# motoko_ice_dragon_x_bldc.net
KiCad netlist of a schematic drawn in EAGLE
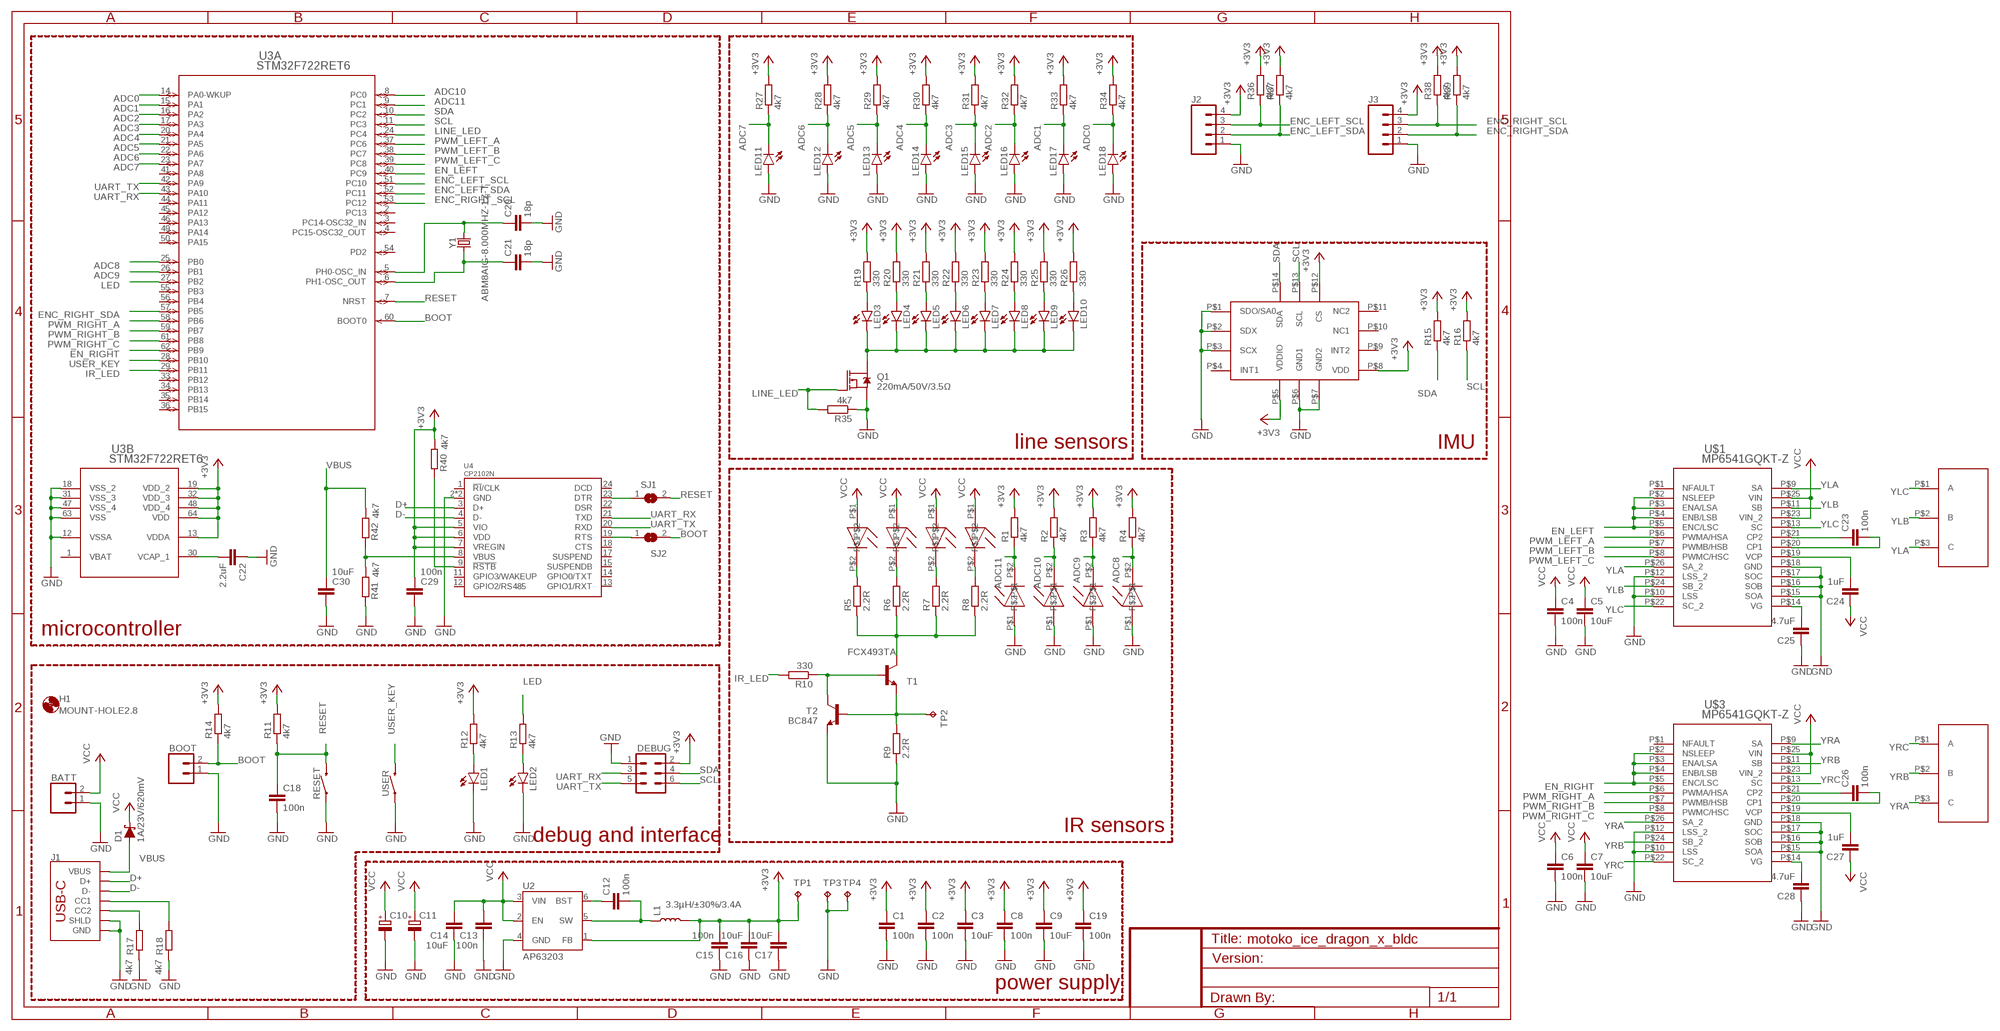
[diagram p0: schematic, sheet 1]

(export (version "E")
  (design (tool "Eeschema 10.0.6"))
  (components
    (comp (ref "BATT")
      (value "CONN_02LOCK_LONGPADS")
      (footprint "eagle-import:1X02_LOCK_LONGPADS")
      (libsource (lib "eagle-import") (part "CONN_02LOCK_LONGPADS"))
    )
    (comp (ref "BOOT")
      (value "CONN_02LOCK_LONGPADS")
      (footprint "eagle-import:1X02_LOCK_LONGPADS")
      (libsource (lib "eagle-import") (part "CONN_02LOCK_LONGPADS"))
    )
    (comp (ref "C1")
      (value "100n")
      (footprint "eagle-import:C0805")
      (libsource (lib "eagle-import") (part "C-EUC0805"))
    )
    (comp (ref "C2")
      (value "100n")
      (footprint "eagle-import:C0805")
      (libsource (lib "eagle-import") (part "C-EUC0805"))
    )
    (comp (ref "C3")
      (value "10uF")
      (footprint "eagle-import:C0805")
      (libsource (lib "eagle-import") (part "C-EUC0805"))
    )
    (comp (ref "C4")
      (value "100n")
      (footprint "eagle-import:C0805")
      (libsource (lib "eagle-import") (part "C-EUC0805"))
    )
    (comp (ref "C5")
      (value "10uF")
      (footprint "eagle-import:C0805")
      (libsource (lib "eagle-import") (part "C-EUC0805"))
    )
    (comp (ref "C6")
      (value "100n")
      (footprint "eagle-import:C0805")
      (libsource (lib "eagle-import") (part "C-EUC0805"))
    )
    (comp (ref "C7")
      (value "10uF")
      (footprint "eagle-import:C0805")
      (libsource (lib "eagle-import") (part "C-EUC0805"))
    )
    (comp (ref "C8")
      (value "100n")
      (footprint "eagle-import:C0805")
      (libsource (lib "eagle-import") (part "C-EUC0805"))
    )
    (comp (ref "C9")
      (value "10uF")
      (footprint "eagle-import:C0805")
      (libsource (lib "eagle-import") (part "C-EUC0805"))
    )
    (comp (ref "C10")
      (value "CPOL-EU140CLH-0810")
      (footprint "eagle-import:140CLH-0810")
      (libsource (lib "eagle-import") (part "CPOL-EU140CLH-0810"))
    )
    (comp (ref "C11")
      (value "CPOL-EU140CLH-0810")
      (footprint "eagle-import:140CLH-0810")
      (libsource (lib "eagle-import") (part "CPOL-EU140CLH-0810"))
    )
    (comp (ref "C12")
      (value "100n")
      (footprint "eagle-import:C0805")
      (libsource (lib "eagle-import") (part "C-EUC0805"))
    )
    (comp (ref "C13")
      (value "100n")
      (footprint "eagle-import:C0805")
      (libsource (lib "eagle-import") (part "C-EUC0805"))
    )
    (comp (ref "C14")
      (value "10uF")
      (footprint "eagle-import:C0805")
      (libsource (lib "eagle-import") (part "C-EUC0805"))
    )
    (comp (ref "C15")
      (value "100n")
      (footprint "eagle-import:C0805")
      (libsource (lib "eagle-import") (part "C-EUC0805"))
    )
    (comp (ref "C16")
      (value "10uF")
      (footprint "eagle-import:C0805")
      (libsource (lib "eagle-import") (part "C-EUC0805"))
    )
    (comp (ref "C17")
      (value "10uF")
      (footprint "eagle-import:C0805")
      (libsource (lib "eagle-import") (part "C-EUC0805"))
    )
    (comp (ref "C18")
      (value "100n")
      (footprint "eagle-import:C0805")
      (libsource (lib "eagle-import") (part "C-EUC0805"))
    )
    (comp (ref "C19")
      (value "100n")
      (footprint "eagle-import:C0805")
      (libsource (lib "eagle-import") (part "C-EUC0805"))
    )
    (comp (ref "C20")
      (value "18p")
      (footprint "eagle-import:C0805")
      (libsource (lib "eagle-import") (part "C-EUC0805"))
    )
    (comp (ref "C21")
      (value "18p")
      (footprint "eagle-import:C0805")
      (libsource (lib "eagle-import") (part "C-EUC0805"))
    )
    (comp (ref "C22")
      (value "2.2uF")
      (footprint "eagle-import:C0805")
      (libsource (lib "eagle-import") (part "C-EUC0805"))
    )
    (comp (ref "C23")
      (value "100n")
      (footprint "eagle-import:C0805")
      (libsource (lib "eagle-import") (part "C-EUC0805"))
    )
    (comp (ref "C24")
      (value "1uF")
      (footprint "eagle-import:C0805")
      (libsource (lib "eagle-import") (part "C-EUC0805"))
    )
    (comp (ref "C25")
      (value "4.7uF")
      (footprint "eagle-import:C0805")
      (libsource (lib "eagle-import") (part "C-EUC0805"))
    )
    (comp (ref "C26")
      (value "100n")
      (footprint "eagle-import:C0805")
      (libsource (lib "eagle-import") (part "C-EUC0805"))
    )
    (comp (ref "C27")
      (value "1uF")
      (footprint "eagle-import:C0805")
      (libsource (lib "eagle-import") (part "C-EUC0805"))
    )
    (comp (ref "C28")
      (value "4.7uF")
      (footprint "eagle-import:C0805")
      (libsource (lib "eagle-import") (part "C-EUC0805"))
    )
    (comp (ref "C29")
      (value "100n")
      (footprint "eagle-import:C0805")
      (libsource (lib "eagle-import") (part "C-EUC0805"))
    )
    (comp (ref "C30")
      (value "10uF")
      (footprint "eagle-import:C0805")
      (libsource (lib "eagle-import") (part "C-EUC0805"))
    )
    (comp (ref "D1")
      (value "1A/23V/620mV")
      (footprint "eagle-import:SOD-323")
      (libsource (lib "eagle-import") (part "DIODE-SCHOTTKY-BAT20J"))
    )
    (comp (ref "DEBUG")
      (value "FEMALE 2x3")
      (footprint "eagle-import:2X3")
      (libsource (lib "eagle-import") (part "CONN_03X2FEMALE"))
    )
    (comp (ref "H1")
      (value "MOUNT-HOLE2.8")
      (footprint "eagle-import:2,8")
      (libsource (lib "eagle-import") (part "MOUNT-HOLE2.8"))
    )
    (comp (ref "J1")
      (value "640-USB4105-GF-A-120, man. GCT")
      (footprint "eagle-import:USB-C-16P-2LAYER-PADS")
      (libsource (lib "eagle-import") (part "USB_C_2-LAYER_PADS"))
    )
    (comp (ref "J2")
      (value "CONN_04LONGPADS")
      (footprint "eagle-import:1X04_LONGPADS")
      (libsource (lib "eagle-import") (part "CONN_04LONGPADS"))
    )
    (comp (ref "J3")
      (value "CONN_04LONGPADS")
      (footprint "eagle-import:1X04_LONGPADS")
      (libsource (lib "eagle-import") (part "CONN_04LONGPADS"))
    )
    (comp (ref "L1")
      (value "3.3µH/±30%/3.4A")
      (footprint "eagle-import:CR54")
      (libsource (lib "eagle-import") (part "INDUCTOR-CR54-3.3UH"))
    )
    (comp (ref "LED1")
      (value "LEDCHIPLED_1206")
      (footprint "eagle-import:CHIPLED_1206")
      (libsource (lib "eagle-import") (part "LEDCHIPLED_1206"))
    )
    (comp (ref "LED2")
      (value "LEDCHIPLED_1206")
      (footprint "eagle-import:CHIPLED_1206")
      (libsource (lib "eagle-import") (part "LEDCHIPLED_1206"))
    )
    (comp (ref "LED3")
      (value "LEDCHIPLED_1206")
      (footprint "eagle-import:CHIPLED_1206")
      (libsource (lib "eagle-import") (part "LEDCHIPLED_1206"))
    )
    (comp (ref "LED4")
      (value "LEDCHIPLED_1206")
      (footprint "eagle-import:CHIPLED_1206")
      (libsource (lib "eagle-import") (part "LEDCHIPLED_1206"))
    )
    (comp (ref "LED5")
      (value "LEDCHIPLED_1206")
      (footprint "eagle-import:CHIPLED_1206")
      (libsource (lib "eagle-import") (part "LEDCHIPLED_1206"))
    )
    (comp (ref "LED6")
      (value "LEDCHIPLED_1206")
      (footprint "eagle-import:CHIPLED_1206")
      (libsource (lib "eagle-import") (part "LEDCHIPLED_1206"))
    )
    (comp (ref "LED7")
      (value "LEDCHIPLED_1206")
      (footprint "eagle-import:CHIPLED_1206")
      (libsource (lib "eagle-import") (part "LEDCHIPLED_1206"))
    )
    (comp (ref "LED8")
      (value "LEDCHIPLED_1206")
      (footprint "eagle-import:CHIPLED_1206")
      (libsource (lib "eagle-import") (part "LEDCHIPLED_1206"))
    )
    (comp (ref "LED9")
      (value "LEDCHIPLED_1206")
      (footprint "eagle-import:CHIPLED_1206")
      (libsource (lib "eagle-import") (part "LEDCHIPLED_1206"))
    )
    (comp (ref "LED10")
      (value "LEDCHIPLED_1206")
      (footprint "eagle-import:CHIPLED_1206")
      (libsource (lib "eagle-import") (part "LEDCHIPLED_1206"))
    )
    (comp (ref "LED11")
      (value "LEDCHIPLED_1206")
      (footprint "eagle-import:CHIPLED_1206")
      (libsource (lib "eagle-import") (part "LEDCHIPLED_1206"))
    )
    (comp (ref "LED12")
      (value "LEDCHIPLED_1206")
      (footprint "eagle-import:CHIPLED_1206")
      (libsource (lib "eagle-import") (part "LEDCHIPLED_1206"))
    )
    (comp (ref "LED13")
      (value "LEDCHIPLED_1206")
      (footprint "eagle-import:CHIPLED_1206")
      (libsource (lib "eagle-import") (part "LEDCHIPLED_1206"))
    )
    (comp (ref "LED14")
      (value "LEDCHIPLED_1206")
      (footprint "eagle-import:CHIPLED_1206")
      (libsource (lib "eagle-import") (part "LEDCHIPLED_1206"))
    )
    (comp (ref "LED15")
      (value "LEDCHIPLED_1206")
      (footprint "eagle-import:CHIPLED_1206")
      (libsource (lib "eagle-import") (part "LEDCHIPLED_1206"))
    )
    (comp (ref "LED16")
      (value "LEDCHIPLED_1206")
      (footprint "eagle-import:CHIPLED_1206")
      (libsource (lib "eagle-import") (part "LEDCHIPLED_1206"))
    )
    (comp (ref "LED17")
      (value "LEDCHIPLED_1206")
      (footprint "eagle-import:CHIPLED_1206")
      (libsource (lib "eagle-import") (part "LEDCHIPLED_1206"))
    )
    (comp (ref "LED18")
      (value "LEDCHIPLED_1206")
      (footprint "eagle-import:CHIPLED_1206")
      (libsource (lib "eagle-import") (part "LEDCHIPLED_1206"))
    )
    (comp (ref "Q1")
      (value "220mA/50V/3.5Ω")
      (footprint "eagle-import:SOT23-3")
      (libsource (lib "eagle-import") (part "MOSFET-NCH-BSS138"))
    )
    (comp (ref "R1")
      (value "4k7")
      (footprint "eagle-import:M0805")
      (libsource (lib "eagle-import") (part "R-EU_M0805"))
    )
    (comp (ref "R2")
      (value "4k7")
      (footprint "eagle-import:M0805")
      (libsource (lib "eagle-import") (part "R-EU_M0805"))
    )
    (comp (ref "R3")
      (value "4k7")
      (footprint "eagle-import:M0805")
      (libsource (lib "eagle-import") (part "R-EU_M0805"))
    )
    (comp (ref "R4")
      (value "4k7")
      (footprint "eagle-import:M0805")
      (libsource (lib "eagle-import") (part "R-EU_M0805"))
    )
    (comp (ref "R5")
      (value "2.2R")
      (footprint "eagle-import:M0805")
      (libsource (lib "eagle-import") (part "R-EU_M0805"))
    )
    (comp (ref "R6")
      (value "2.2R")
      (footprint "eagle-import:M0805")
      (libsource (lib "eagle-import") (part "R-EU_M0805"))
    )
    (comp (ref "R7")
      (value "2.2R")
      (footprint "eagle-import:M0805")
      (libsource (lib "eagle-import") (part "R-EU_M0805"))
    )
    (comp (ref "R8")
      (value "2.2R")
      (footprint "eagle-import:M0805")
      (libsource (lib "eagle-import") (part "R-EU_M0805"))
    )
    (comp (ref "R9")
      (value "2.2R")
      (footprint "eagle-import:M0805")
      (libsource (lib "eagle-import") (part "R-EU_M0805"))
    )
    (comp (ref "R10")
      (value "330")
      (footprint "eagle-import:M0805")
      (libsource (lib "eagle-import") (part "R-EU_M0805"))
    )
    (comp (ref "R11")
      (value "4k7")
      (footprint "eagle-import:M0805")
      (libsource (lib "eagle-import") (part "R-EU_M0805"))
    )
    (comp (ref "R12")
      (value "4k7")
      (footprint "eagle-import:M0805")
      (libsource (lib "eagle-import") (part "R-EU_M0805"))
    )
    (comp (ref "R13")
      (value "4k7")
      (footprint "eagle-import:M0805")
      (libsource (lib "eagle-import") (part "R-EU_M0805"))
    )
    (comp (ref "R14")
      (value "4k7")
      (footprint "eagle-import:M0805")
      (libsource (lib "eagle-import") (part "R-EU_M0805"))
    )
    (comp (ref "R15")
      (value "4k7")
      (footprint "eagle-import:M0805")
      (libsource (lib "eagle-import") (part "R-EU_M0805"))
    )
    (comp (ref "R16")
      (value "4k7")
      (footprint "eagle-import:M0805")
      (libsource (lib "eagle-import") (part "R-EU_M0805"))
    )
    (comp (ref "R17")
      (value "4k7")
      (footprint "eagle-import:M0805")
      (libsource (lib "eagle-import") (part "R-EU_M0805"))
    )
    (comp (ref "R18")
      (value "4k7")
      (footprint "eagle-import:M0805")
      (libsource (lib "eagle-import") (part "R-EU_M0805"))
    )
    (comp (ref "R19")
      (value "330")
      (footprint "eagle-import:M0805")
      (libsource (lib "eagle-import") (part "R-EU_M0805"))
    )
    (comp (ref "R20")
      (value "330")
      (footprint "eagle-import:M0805")
      (libsource (lib "eagle-import") (part "R-EU_M0805"))
    )
    (comp (ref "R21")
      (value "330")
      (footprint "eagle-import:M0805")
      (libsource (lib "eagle-import") (part "R-EU_M0805"))
    )
    (comp (ref "R22")
      (value "330")
      (footprint "eagle-import:M0805")
      (libsource (lib "eagle-import") (part "R-EU_M0805"))
    )
    (comp (ref "R23")
      (value "330")
      (footprint "eagle-import:M0805")
      (libsource (lib "eagle-import") (part "R-EU_M0805"))
    )
    (comp (ref "R24")
      (value "330")
      (footprint "eagle-import:M0805")
      (libsource (lib "eagle-import") (part "R-EU_M0805"))
    )
    (comp (ref "R25")
      (value "330")
      (footprint "eagle-import:M0805")
      (libsource (lib "eagle-import") (part "R-EU_M0805"))
    )
    (comp (ref "R26")
      (value "330")
      (footprint "eagle-import:M0805")
      (libsource (lib "eagle-import") (part "R-EU_M0805"))
    )
    (comp (ref "R27")
      (value "4k7")
      (footprint "eagle-import:M0805")
      (libsource (lib "eagle-import") (part "R-EU_M0805"))
    )
    (comp (ref "R28")
      (value "4k7")
      (footprint "eagle-import:M0805")
      (libsource (lib "eagle-import") (part "R-EU_M0805"))
    )
    (comp (ref "R29")
      (value "4k7")
      (footprint "eagle-import:M0805")
      (libsource (lib "eagle-import") (part "R-EU_M0805"))
    )
    (comp (ref "R30")
      (value "4k7")
      (footprint "eagle-import:M0805")
      (libsource (lib "eagle-import") (part "R-EU_M0805"))
    )
    (comp (ref "R31")
      (value "4k7")
      (footprint "eagle-import:M0805")
      (libsource (lib "eagle-import") (part "R-EU_M0805"))
    )
    (comp (ref "R32")
      (value "4k7")
      (footprint "eagle-import:M0805")
      (libsource (lib "eagle-import") (part "R-EU_M0805"))
    )
    (comp (ref "R33")
      (value "4k7")
      (footprint "eagle-import:M0805")
      (libsource (lib "eagle-import") (part "R-EU_M0805"))
    )
    (comp (ref "R34")
      (value "4k7")
      (footprint "eagle-import:M0805")
      (libsource (lib "eagle-import") (part "R-EU_M0805"))
    )
    (comp (ref "R35")
      (value "4k7")
      (footprint "eagle-import:M0805")
      (libsource (lib "eagle-import") (part "R-EU_M0805"))
    )
    (comp (ref "R36")
      (value "4k7")
      (footprint "eagle-import:M0805")
      (libsource (lib "eagle-import") (part "R-EU_M0805"))
    )
    (comp (ref "R37")
      (value "4k7")
      (footprint "eagle-import:M0805")
      (libsource (lib "eagle-import") (part "R-EU_M0805"))
    )
    (comp (ref "R38")
      (value "4k7")
      (footprint "eagle-import:M0805")
      (libsource (lib "eagle-import") (part "R-EU_M0805"))
    )
    (comp (ref "R39")
      (value "4k7")
      (footprint "eagle-import:M0805")
      (libsource (lib "eagle-import") (part "R-EU_M0805"))
    )
    (comp (ref "R40")
      (value "4k7")
      (footprint "eagle-import:M0805")
      (libsource (lib "eagle-import") (part "R-EU_M0805"))
    )
    (comp (ref "R41")
      (value "4k7")
      (footprint "eagle-import:M0805")
      (libsource (lib "eagle-import") (part "R-EU_M0805"))
    )
    (comp (ref "R42")
      (value "4k7")
      (footprint "eagle-import:M0805")
      (libsource (lib "eagle-import") (part "R-EU_M0805"))
    )
    (comp (ref "RESET")
      (value "MOMENTARY-SWITCH-SPST-SMD-6.2MM-TALL")
      (footprint "eagle-import:TACTILE_SWITCH_SMD_6.2MM_TALL")
      (libsource (lib "eagle-import") (part "MOMENTARY-SWITCH-SPST-SMD-6.2MM-TALL"))
    )
    (comp (ref "SJ1") (value "SJ") (footprint "eagle-import:SJ") (libsource (lib "eagle-import") (part "SJ")))
    (comp (ref "SJ2") (value "SJ") (footprint "eagle-import:SJ") (libsource (lib "eagle-import") (part "SJ")))
    (comp (ref "T1")
      (value "FCX493TA")
      (footprint "eagle-import:SOT89-BCE")
      (libsource (lib "eagle-import") (part "-NPN-SOT89-BCE"))
    )
    (comp (ref "T2")
      (value "BC847")
      (footprint "eagle-import:SOT23")
      (libsource (lib "eagle-import") (part "BC847"))
    )
    (comp (ref "TP1")
      (value "TPB1,27")
      (footprint "eagle-import:B1,27")
      (libsource (lib "eagle-import") (part "TPB1,27"))
    )
    (comp (ref "TP2")
      (value "TPB1,27")
      (footprint "eagle-import:B1,27")
      (libsource (lib "eagle-import") (part "TPB1,27"))
    )
    (comp (ref "TP3")
      (value "TPB1,27")
      (footprint "eagle-import:B1,27")
      (libsource (lib "eagle-import") (part "TPB1,27"))
    )
    (comp (ref "TP4")
      (value "TPB1,27")
      (footprint "eagle-import:B1,27")
      (libsource (lib "eagle-import") (part "TPB1,27"))
    )
    (comp (ref "U$1")
      (value "MP6541GQKT-Z")
      (footprint "eagle-import:TQFN-26")
      (libsource (lib "eagle-import") (part "MP6541GQKT-Z"))
    )
    (comp (ref "U$2")
      (value "BRUSHLESS_GIMBAL_MOTOR_WHEEL")
      (footprint "eagle-import:BRUSHLESS_GIMBAL_MOTOR_WHEEL")
      (libsource (lib "eagle-import") (part "BRUSHLESS_GIMBAL_MOTOR_WHEEL"))
    )
    (comp (ref "U$3")
      (value "MP6541GQKT-Z")
      (footprint "eagle-import:TQFN-26")
      (libsource (lib "eagle-import") (part "MP6541GQKT-Z"))
    )
    (comp (ref "U$4")
      (value "BRUSHLESS_GIMBAL_MOTOR_WHEEL")
      (footprint "eagle-import:BRUSHLESS_GIMBAL_MOTOR_WHEEL")
      (libsource (lib "eagle-import") (part "BRUSHLESS_GIMBAL_MOTOR_WHEEL"))
    )
    (comp (ref "U$6")
      (value "LSM6DSM")
      (footprint "eagle-import:LGA14L")
      (libsource (lib "eagle-import") (part "LSM6DSM"))
    )
    (comp (ref "U$7")
      (value "LED_5MM_AXIAL")
      (footprint "eagle-import:LED_5MM_AXIAL")
      (libsource (lib "eagle-import") (part "LED_5MM_AXIAL"))
    )
    (comp (ref "U$8")
      (value "LED_5MM_AXIAL")
      (footprint "eagle-import:LED_5MM_AXIAL")
      (libsource (lib "eagle-import") (part "LED_5MM_AXIAL"))
    )
    (comp (ref "U$9")
      (value "LED_5MM_AXIAL")
      (footprint "eagle-import:LED_5MM_AXIAL")
      (libsource (lib "eagle-import") (part "LED_5MM_AXIAL"))
    )
    (comp (ref "U$10")
      (value "LED_5MM_AXIAL")
      (footprint "eagle-import:LED_5MM_AXIAL")
      (libsource (lib "eagle-import") (part "LED_5MM_AXIAL"))
    )
    (comp (ref "U$11")
      (value "LED_5MM_AXIAL")
      (footprint "eagle-import:LED_5MM_AXIAL")
      (libsource (lib "eagle-import") (part "LED_5MM_AXIAL"))
    )
    (comp (ref "U$12")
      (value "LED_5MM_AXIAL")
      (footprint "eagle-import:LED_5MM_AXIAL")
      (fields (field (name "SPICEPREFIX") "B"))
      (libsource (lib "eagle-import") (part "LED_5MM_AXIAL"))
    )
    (comp (ref "U$13")
      (value "LED_5MM_AXIAL")
      (footprint "eagle-import:LED_5MM_AXIAL")
      (libsource (lib "eagle-import") (part "LED_5MM_AXIAL"))
    )
    (comp (ref "U$14")
      (value "LED_5MM_AXIAL")
      (footprint "eagle-import:LED_5MM_AXIAL")
      (libsource (lib "eagle-import") (part "LED_5MM_AXIAL"))
    )
    (comp (ref "U2")
      (value "AP63203")
      (footprint "eagle-import:SOT23-6")
      (libsource (lib "eagle-import") (part "AP63203"))
    )
    (comp (ref "U3")
      (value "STM32F722RET6")
      (footprint "eagle-import:LQFP64-10X10MM")
      (fields (field (name "COPYRIGHT") "Copyright (C) 2024 Ultra Librarian. All rights reserved."))
      (libsource (lib "eagle-import") (part "STM32F722RET6"))
    )
    (comp (ref "U4")
      (value "CP2102N")
      (footprint "eagle-import:QFN24")
      (libsource (lib "eagle-import") (part "CP2102N"))
    )
    (comp (ref "USER")
      (value "MOMENTARY-SWITCH-SPST-SMD-6.2MM-TALL")
      (footprint "eagle-import:TACTILE_SWITCH_SMD_6.2MM_TALL")
      (libsource (lib "eagle-import") (part "MOMENTARY-SWITCH-SPST-SMD-6.2MM-TALL"))
    )
    (comp (ref "Y1")
      (value "ABM8AIG-8.000MHZ-1Z-T")
      (footprint "eagle-import:CRYSTAL-SMD-3.2X2.5MM")
      (libsource (lib "eagle-import") (part "CRYSTALSMD-3.2X2.5"))
    )
  )
  (nets
    (net (code "1") (name "+3V3") (class "Default")
      (node (ref "C1") (pin "1") (pinfunction "1_1") (pintype "passive"))
      (node (ref "C15") (pin "2") (pinfunction "2_2") (pintype "passive"))
      (node (ref "C16") (pin "2") (pinfunction "2_2") (pintype "passive"))
      (node (ref "C17") (pin "2") (pinfunction "2_2") (pintype "passive"))
      (node (ref "C19") (pin "1") (pinfunction "1_1") (pintype "passive"))
      (node (ref "C2") (pin "1") (pinfunction "1_1") (pintype "passive"))
      (node (ref "C29") (pin "1") (pinfunction "1_1") (pintype "passive"))
      (node (ref "C3") (pin "1") (pinfunction "1_1") (pintype "passive"))
      (node (ref "C8") (pin "1") (pinfunction "1_1") (pintype "passive"))
      (node (ref "C9") (pin "1") (pinfunction "1_1") (pintype "passive"))
      (node (ref "DEBUG") (pin "2") (pinfunction "2_2") (pintype "bidirectional"))
      (node (ref "J2") (pin "4") (pinfunction "4_4") (pintype "passive"))
      (node (ref "J3") (pin "4") (pinfunction "4_4") (pintype "passive"))
      (node (ref "L1") (pin "P$2") (pinfunction "2_P$2") (pintype "passive"))
      (node (ref "R1") (pin "2") (pinfunction "2_2") (pintype "passive"))
      (node (ref "R11") (pin "2") (pinfunction "2_2") (pintype "passive"))
      (node (ref "R12") (pin "2") (pinfunction "2_2") (pintype "passive"))
      (node (ref "R14") (pin "2") (pinfunction "2_2") (pintype "passive"))
      (node (ref "R15") (pin "2") (pinfunction "2_2") (pintype "passive"))
      (node (ref "R16") (pin "2") (pinfunction "2_2") (pintype "passive"))
      (node (ref "R19") (pin "2") (pinfunction "2_2") (pintype "passive"))
      (node (ref "R2") (pin "2") (pinfunction "2_2") (pintype "passive"))
      (node (ref "R20") (pin "2") (pinfunction "2_2") (pintype "passive"))
      (node (ref "R21") (pin "2") (pinfunction "2_2") (pintype "passive"))
      (node (ref "R22") (pin "2") (pinfunction "2_2") (pintype "passive"))
      (node (ref "R23") (pin "2") (pinfunction "2_2") (pintype "passive"))
      (node (ref "R24") (pin "2") (pinfunction "2_2") (pintype "passive"))
      (node (ref "R25") (pin "2") (pinfunction "2_2") (pintype "passive"))
      (node (ref "R26") (pin "2") (pinfunction "2_2") (pintype "passive"))
      (node (ref "R27") (pin "2") (pinfunction "2_2") (pintype "passive"))
      (node (ref "R28") (pin "2") (pinfunction "2_2") (pintype "passive"))
      (node (ref "R29") (pin "2") (pinfunction "2_2") (pintype "passive"))
      (node (ref "R3") (pin "2") (pinfunction "2_2") (pintype "passive"))
      (node (ref "R30") (pin "2") (pinfunction "2_2") (pintype "passive"))
      (node (ref "R31") (pin "2") (pinfunction "2_2") (pintype "passive"))
      (node (ref "R32") (pin "2") (pinfunction "2_2") (pintype "passive"))
      (node (ref "R33") (pin "2") (pinfunction "2_2") (pintype "passive"))
      (node (ref "R34") (pin "2") (pinfunction "2_2") (pintype "passive"))
      (node (ref "R36") (pin "2") (pinfunction "2_2") (pintype "passive"))
      (node (ref "R37") (pin "2") (pinfunction "2_2") (pintype "passive"))
      (node (ref "R38") (pin "2") (pinfunction "2_2") (pintype "passive"))
      (node (ref "R39") (pin "2") (pinfunction "2_2") (pintype "passive"))
      (node (ref "R4") (pin "2") (pinfunction "2_2") (pintype "passive"))
      (node (ref "R40") (pin "1") (pinfunction "1_1") (pintype "passive"))
      (node (ref "TP1") (pin "TP") (pinfunction "TP_TP") (pintype "input"))
      (node (ref "U$6") (pin "P$12") (pinfunction "CS_P$12") (pintype "bidirectional"))
      (node (ref "U$6") (pin "P$5") (pinfunction "VDDIO_P$5") (pintype "bidirectional"))
      (node (ref "U$6") (pin "P$8") (pinfunction "VDD_P$8") (pintype "bidirectional"))
      (node (ref "U2") (pin "1") (pinfunction "FB_1") (pintype "bidirectional"))
      (node (ref "U3") (pin "13") (pinfunction "VDDA_13") (pintype "power_in"))
      (node (ref "U3") (pin "19") (pinfunction "VDD_2_19") (pintype "power_in"))
      (node (ref "U3") (pin "32") (pinfunction "VDD_3_32") (pintype "power_in"))
      (node (ref "U3") (pin "48") (pinfunction "VDD_4_48") (pintype "power_in"))
      (node (ref "U3") (pin "64") (pinfunction "VDD_64") (pintype "power_in"))
      (node (ref "U4") (pin "5") (pinfunction "VIO_5") (pintype "bidirectional"))
      (node (ref "U4") (pin "6") (pinfunction "VDD_6") (pintype "bidirectional"))
      (node (ref "U4") (pin "7") (pinfunction "VREGIN_7") (pintype "bidirectional"))
    )
    (net (code "2") (name "/ADC0") (class "Default")
      (node (ref "LED18") (pin "C") (pinfunction "C_C") (pintype "passive"))
      (node (ref "R34") (pin "1") (pinfunction "1_1") (pintype "passive"))
      (node (ref "U3") (pin "14") (pinfunction "PA0-WKUP_14") (pintype "bidirectional"))
    )
    (net (code "3") (name "/ADC1") (class "Default")
      (node (ref "LED17") (pin "C") (pinfunction "C_C") (pintype "passive"))
      (node (ref "R33") (pin "1") (pinfunction "1_1") (pintype "passive"))
      (node (ref "U3") (pin "15") (pinfunction "PA1_15") (pintype "bidirectional"))
    )
    (net (code "4") (name "/ADC2") (class "Default")
      (node (ref "LED16") (pin "C") (pinfunction "C_C") (pintype "passive"))
      (node (ref "R32") (pin "1") (pinfunction "1_1") (pintype "passive"))
      (node (ref "U3") (pin "16") (pinfunction "PA2_16") (pintype "bidirectional"))
    )
    (net (code "5") (name "/ADC3") (class "Default")
      (node (ref "LED15") (pin "C") (pinfunction "C_C") (pintype "passive"))
      (node (ref "R31") (pin "1") (pinfunction "1_1") (pintype "passive"))
      (node (ref "U3") (pin "17") (pinfunction "PA3_17") (pintype "bidirectional"))
    )
    (net (code "6") (name "/ADC4") (class "Default")
      (node (ref "LED14") (pin "C") (pinfunction "C_C") (pintype "passive"))
      (node (ref "R30") (pin "1") (pinfunction "1_1") (pintype "passive"))
      (node (ref "U3") (pin "20") (pinfunction "PA4_20") (pintype "bidirectional"))
    )
    (net (code "7") (name "/ADC5") (class "Default")
      (node (ref "LED13") (pin "C") (pinfunction "C_C") (pintype "passive"))
      (node (ref "R29") (pin "1") (pinfunction "1_1") (pintype "passive"))
      (node (ref "U3") (pin "21") (pinfunction "PA5_21") (pintype "bidirectional"))
    )
    (net (code "8") (name "/ADC6") (class "Default")
      (node (ref "LED12") (pin "C") (pinfunction "C_C") (pintype "passive"))
      (node (ref "R28") (pin "1") (pinfunction "1_1") (pintype "passive"))
      (node (ref "U3") (pin "22") (pinfunction "PA6_22") (pintype "bidirectional"))
    )
    (net (code "9") (name "/ADC7") (class "Default")
      (node (ref "LED11") (pin "C") (pinfunction "C_C") (pintype "passive"))
      (node (ref "R27") (pin "1") (pinfunction "1_1") (pintype "passive"))
      (node (ref "U3") (pin "23") (pinfunction "PA7_23") (pintype "bidirectional"))
    )
    (net (code "10") (name "/ADC8") (class "Default")
      (node (ref "R4") (pin "1") (pinfunction "1_1") (pintype "passive"))
      (node (ref "U$7") (pin "P$2") (pinfunction "P$2_P$2") (pintype "bidirectional"))
      (node (ref "U3") (pin "25") (pinfunction "PB0_25") (pintype "bidirectional"))
    )
    (net (code "11") (name "/ADC9") (class "Default")
      (node (ref "R3") (pin "1") (pinfunction "1_1") (pintype "passive"))
      (node (ref "U$11") (pin "P$2") (pinfunction "P$2_P$2") (pintype "bidirectional"))
      (node (ref "U3") (pin "26") (pinfunction "PB1_26") (pintype "bidirectional"))
    )
    (net (code "12") (name "/ADC10") (class "Default")
      (node (ref "R2") (pin "1") (pinfunction "1_1") (pintype "passive"))
      (node (ref "U$14") (pin "P$2") (pinfunction "P$2_P$2") (pintype "bidirectional"))
      (node (ref "U3") (pin "8") (pinfunction "PC0_8") (pintype "bidirectional"))
    )
    (net (code "13") (name "/ADC11") (class "Default")
      (node (ref "R1") (pin "1") (pinfunction "1_1") (pintype "passive"))
      (node (ref "U$9") (pin "P$2") (pinfunction "P$2_P$2") (pintype "bidirectional"))
      (node (ref "U3") (pin "9") (pinfunction "PC1_9") (pintype "bidirectional"))
    )
    (net (code "14") (name "/BOOT") (class "Default")
      (node (ref "BOOT") (pin "2") (pinfunction "2_2") (pintype "passive"))
      (node (ref "R14") (pin "1") (pinfunction "1_1") (pintype "passive"))
      (node (ref "SJ2") (pin "2") (pinfunction "2_2") (pintype "passive"))
      (node (ref "U3") (pin "60") (pinfunction "BOOT0_60") (pintype "input"))
    )
    (net (code "15") (name "/D+") (class "Default")
      (node (ref "J1") (pin "A6") (pinfunction "D+_A6") (pintype "bidirectional"))
      (node (ref "J1") (pin "B6") (pinfunction "D+_B6") (pintype "bidirectional"))
      (node (ref "U4") (pin "3") (pinfunction "D+_3") (pintype "bidirectional"))
    )
    (net (code "16") (name "/D-") (class "Default")
      (node (ref "J1") (pin "A7") (pinfunction "D-_A7") (pintype "bidirectional"))
      (node (ref "J1") (pin "B7") (pinfunction "D-_B7") (pintype "bidirectional"))
      (node (ref "U4") (pin "4") (pinfunction "D-_4") (pintype "bidirectional"))
    )
    (net (code "17") (name "/ENC_LEFT_SCL") (class "Default")
      (node (ref "J2") (pin "3") (pinfunction "3_3") (pintype "passive"))
      (node (ref "R36") (pin "1") (pinfunction "1_1") (pintype "passive"))
      (node (ref "U3") (pin "51") (pinfunction "PC10_51") (pintype "bidirectional"))
    )
    (net (code "18") (name "/ENC_LEFT_SDA") (class "Default")
      (node (ref "J2") (pin "2") (pinfunction "2_2") (pintype "passive"))
      (node (ref "R37") (pin "1") (pinfunction "1_1") (pintype "passive"))
      (node (ref "U3") (pin "52") (pinfunction "PC11_52") (pintype "bidirectional"))
    )
    (net (code "19") (name "/ENC_RIGHT_SCL") (class "Default")
      (node (ref "J3") (pin "3") (pinfunction "3_3") (pintype "passive"))
      (node (ref "R38") (pin "1") (pinfunction "1_1") (pintype "passive"))
      (node (ref "U3") (pin "53") (pinfunction "PC12_53") (pintype "bidirectional"))
    )
    (net (code "20") (name "/ENC_RIGHT_SDA") (class "Default")
      (node (ref "J3") (pin "2") (pinfunction "2_2") (pintype "passive"))
      (node (ref "R39") (pin "1") (pinfunction "1_1") (pintype "passive"))
      (node (ref "U3") (pin "57") (pinfunction "PB5_57") (pintype "bidirectional"))
    )
    (net (code "21") (name "/EN_LEFT") (class "Default")
      (node (ref "U$1") (pin "P$2") (pinfunction "NSLEEP_P$2") (pintype "input"))
      (node (ref "U$1") (pin "P$3") (pinfunction "ENA/LSA_P$3") (pintype "passive"))
      (node (ref "U$1") (pin "P$4") (pinfunction "ENB/LSB_P$4") (pintype "passive"))
      (node (ref "U$1") (pin "P$5") (pinfunction "ENC/LSC_P$5") (pintype "passive"))
      (node (ref "U3") (pin "40") (pinfunction "PC9_40") (pintype "bidirectional"))
    )
    (net (code "22") (name "/EN_RIGHT") (class "Default")
      (node (ref "U$3") (pin "P$2") (pinfunction "NSLEEP_P$2") (pintype "input"))
      (node (ref "U$3") (pin "P$3") (pinfunction "ENA/LSA_P$3") (pintype "passive"))
      (node (ref "U$3") (pin "P$4") (pinfunction "ENB/LSB_P$4") (pintype "passive"))
      (node (ref "U$3") (pin "P$5") (pinfunction "ENC/LSC_P$5") (pintype "passive"))
      (node (ref "U3") (pin "62") (pinfunction "PB9_62") (pintype "bidirectional"))
    )
    (net (code "23") (name "/IR_LED") (class "Default")
      (node (ref "R10") (pin "2") (pinfunction "2_2") (pintype "passive"))
      (node (ref "U3") (pin "29") (pinfunction "PB11_29") (pintype "bidirectional"))
    )
    (net (code "24") (name "/LED") (class "Default")
      (node (ref "R13") (pin "2") (pinfunction "2_2") (pintype "passive"))
      (node (ref "U3") (pin "27") (pinfunction "PB2_27") (pintype "bidirectional"))
    )
    (net (code "25") (name "/LINE_LED") (class "Default")
      (node (ref "Q1") (pin "1") (pinfunction "G_1") (pintype "bidirectional"))
      (node (ref "R35") (pin "2") (pinfunction "2_2") (pintype "passive"))
      (node (ref "U3") (pin "24") (pinfunction "PC4_24") (pintype "bidirectional"))
    )
    (net (code "26") (name "/PWM_LEFT_A") (class "Default")
      (node (ref "U$1") (pin "P$6") (pinfunction "PWMA/HSA_P$6") (pintype "passive"))
      (node (ref "U3") (pin "37") (pinfunction "PC6_37") (pintype "bidirectional"))
    )
    (net (code "27") (name "/PWM_LEFT_B") (class "Default")
      (node (ref "U$1") (pin "P$7") (pinfunction "PWMB/HSB_P$7") (pintype "passive"))
      (node (ref "U3") (pin "38") (pinfunction "PC7_38") (pintype "bidirectional"))
    )
    (net (code "28") (name "/PWM_LEFT_C") (class "Default")
      (node (ref "U$1") (pin "P$8") (pinfunction "PWMC/HSC_P$8") (pintype "passive"))
      (node (ref "U3") (pin "39") (pinfunction "PC8_39") (pintype "bidirectional"))
    )
    (net (code "29") (name "/PWM_RIGHT_A") (class "Default")
      (node (ref "U$3") (pin "P$6") (pinfunction "PWMA/HSA_P$6") (pintype "passive"))
      (node (ref "U3") (pin "58") (pinfunction "PB6_58") (pintype "bidirectional"))
    )
    (net (code "30") (name "/PWM_RIGHT_B") (class "Default")
      (node (ref "U$3") (pin "P$7") (pinfunction "PWMB/HSB_P$7") (pintype "passive"))
      (node (ref "U3") (pin "59") (pinfunction "PB7_59") (pintype "bidirectional"))
    )
    (net (code "31") (name "/PWM_RIGHT_C") (class "Default")
      (node (ref "U$3") (pin "P$8") (pinfunction "PWMC/HSC_P$8") (pintype "passive"))
      (node (ref "U3") (pin "61") (pinfunction "PB8_61") (pintype "bidirectional"))
    )
    (net (code "32") (name "/RESET") (class "Default")
      (node (ref "C18") (pin "1") (pinfunction "1_1") (pintype "passive"))
      (node (ref "R11") (pin "1") (pinfunction "1_1") (pintype "passive"))
      (node (ref "RESET") (pin "B2") (pinfunction "2_B2") (pintype "passive"))
      (node (ref "SJ1") (pin "2") (pinfunction "2_2") (pintype "passive"))
      (node (ref "U3") (pin "7") (pinfunction "NRST_7") (pintype "bidirectional"))
    )
    (net (code "33") (name "/SCL") (class "Default")
      (node (ref "DEBUG") (pin "6") (pinfunction "6_6") (pintype "bidirectional"))
      (node (ref "R16") (pin "1") (pinfunction "1_1") (pintype "passive"))
      (node (ref "U$6") (pin "P$13") (pinfunction "SCL_P$13") (pintype "bidirectional"))
      (node (ref "U3") (pin "11") (pinfunction "PC3_11") (pintype "bidirectional"))
    )
    (net (code "34") (name "/SDA") (class "Default")
      (node (ref "DEBUG") (pin "4") (pinfunction "4_4") (pintype "bidirectional"))
      (node (ref "R15") (pin "1") (pinfunction "1_1") (pintype "passive"))
      (node (ref "U$6") (pin "P$14") (pinfunction "SDA_P$14") (pintype "bidirectional"))
      (node (ref "U3") (pin "10") (pinfunction "PC2_10") (pintype "bidirectional"))
    )
    (net (code "35") (name "/UART_RX") (class "Default")
      (node (ref "DEBUG") (pin "3") (pinfunction "3_3") (pintype "bidirectional"))
      (node (ref "U3") (pin "43") (pinfunction "PA10_43") (pintype "bidirectional"))
      (node (ref "U4") (pin "21") (pinfunction "TXD_21") (pintype "bidirectional"))
    )
    (net (code "36") (name "/UART_TX") (class "Default")
      (node (ref "DEBUG") (pin "5") (pinfunction "5_5") (pintype "bidirectional"))
      (node (ref "U3") (pin "42") (pinfunction "PA9_42") (pintype "bidirectional"))
      (node (ref "U4") (pin "20") (pinfunction "RXD_20") (pintype "bidirectional"))
    )
    (net (code "37") (name "/USER_KEY") (class "Default")
      (node (ref "U3") (pin "28") (pinfunction "PB10_28") (pintype "bidirectional"))
      (node (ref "USER") (pin "B2") (pinfunction "2_B2") (pintype "passive"))
    )
    (net (code "38") (name "/VBAT") (class "Default")
      (node (ref "U3") (pin "1") (pinfunction "VBAT_1") (pintype "power_in"))
    )
    (net (code "39") (name "/VBUS") (class "Default")
      (node (ref "C30") (pin "1") (pinfunction "1_1") (pintype "passive"))
      (node (ref "D1") (pin "A") (pinfunction "A_A") (pintype "passive"))
      (node (ref "J1") (pin "VBUS1") (pinfunction "VBUS_VBUS1") (pintype "bidirectional"))
      (node (ref "J1") (pin "VBUS2") (pinfunction "VBUS_VBUS2") (pintype "bidirectional"))
      (node (ref "R42") (pin "1") (pinfunction "1_1") (pintype "passive"))
    )
    (net (code "40") (name "/YLA") (class "Default")
      (node (ref "U$1") (pin "P$26") (pinfunction "SA_2_P$26") (pintype "output"))
      (node (ref "U$1") (pin "P$9") (pinfunction "SA_P$9") (pintype "output"))
      (node (ref "U$2") (pin "P$3") (pinfunction "C_P$3") (pintype "input"))
    )
    (net (code "41") (name "/YLB") (class "Default")
      (node (ref "U$1") (pin "P$11") (pinfunction "SB_P$11") (pintype "output"))
      (node (ref "U$1") (pin "P$24") (pinfunction "SB_2_P$24") (pintype "output"))
      (node (ref "U$2") (pin "P$2") (pinfunction "B_P$2") (pintype "input"))
    )
    (net (code "42") (name "/YLC") (class "Default")
      (node (ref "U$1") (pin "P$13") (pinfunction "SC_P$13") (pintype "output"))
      (node (ref "U$1") (pin "P$22") (pinfunction "SC_2_P$22") (pintype "output"))
      (node (ref "U$2") (pin "P$1") (pinfunction "A_P$1") (pintype "input"))
    )
    (net (code "43") (name "/YRA") (class "Default")
      (node (ref "U$3") (pin "P$26") (pinfunction "SA_2_P$26") (pintype "output"))
      (node (ref "U$3") (pin "P$9") (pinfunction "SA_P$9") (pintype "output"))
      (node (ref "U$4") (pin "P$3") (pinfunction "C_P$3") (pintype "input"))
    )
    (net (code "44") (name "/YRB") (class "Default")
      (node (ref "U$3") (pin "P$11") (pinfunction "SB_P$11") (pintype "output"))
      (node (ref "U$3") (pin "P$24") (pinfunction "SB_2_P$24") (pintype "output"))
      (node (ref "U$4") (pin "P$2") (pinfunction "B_P$2") (pintype "input"))
    )
    (net (code "45") (name "/YRC") (class "Default")
      (node (ref "U$3") (pin "P$13") (pinfunction "SC_P$13") (pintype "output"))
      (node (ref "U$3") (pin "P$22") (pinfunction "SC_2_P$22") (pintype "output"))
      (node (ref "U$4") (pin "P$1") (pinfunction "A_P$1") (pintype "input"))
    )
    (net (code "46") (name "GND") (class "Default")
      (node (ref "BATT") (pin "1") (pinfunction "1_1") (pintype "passive"))
      (node (ref "BOOT") (pin "1") (pinfunction "1_1") (pintype "passive"))
      (node (ref "C1") (pin "2") (pinfunction "2_2") (pintype "passive"))
      (node (ref "C10") (pin "-") (pinfunction "-_-") (pintype "passive"))
      (node (ref "C11") (pin "-") (pinfunction "-_-") (pintype "passive"))
      (node (ref "C13") (pin "1") (pinfunction "1_1") (pintype "passive"))
      (node (ref "C14") (pin "1") (pinfunction "1_1") (pintype "passive"))
      (node (ref "C15") (pin "1") (pinfunction "1_1") (pintype "passive"))
      (node (ref "C16") (pin "1") (pinfunction "1_1") (pintype "passive"))
      (node (ref "C17") (pin "1") (pinfunction "1_1") (pintype "passive"))
      (node (ref "C18") (pin "2") (pinfunction "2_2") (pintype "passive"))
      (node (ref "C19") (pin "2") (pinfunction "2_2") (pintype "passive"))
      (node (ref "C2") (pin "2") (pinfunction "2_2") (pintype "passive"))
      (node (ref "C20") (pin "2") (pinfunction "2_2") (pintype "passive"))
      (node (ref "C21") (pin "2") (pinfunction "2_2") (pintype "passive"))
      (node (ref "C22") (pin "1") (pinfunction "1_1") (pintype "passive"))
      (node (ref "C25") (pin "1") (pinfunction "1_1") (pintype "passive"))
      (node (ref "C28") (pin "1") (pinfunction "1_1") (pintype "passive"))
      (node (ref "C29") (pin "2") (pinfunction "2_2") (pintype "passive"))
      (node (ref "C3") (pin "2") (pinfunction "2_2") (pintype "passive"))
      (node (ref "C30") (pin "2") (pinfunction "2_2") (pintype "passive"))
      (node (ref "C4") (pin "2") (pinfunction "2_2") (pintype "passive"))
      (node (ref "C5") (pin "2") (pinfunction "2_2") (pintype "passive"))
      (node (ref "C6") (pin "2") (pinfunction "2_2") (pintype "passive"))
      (node (ref "C7") (pin "2") (pinfunction "2_2") (pintype "passive"))
      (node (ref "C8") (pin "2") (pinfunction "2_2") (pintype "passive"))
      (node (ref "C9") (pin "2") (pinfunction "2_2") (pintype "passive"))
      (node (ref "DEBUG") (pin "1") (pinfunction "1_1") (pintype "bidirectional"))
      (node (ref "J1") (pin "GND") (pinfunction "GND_GND") (pintype "bidirectional"))
      (node (ref "J1") (pin "GND2") (pinfunction "GND_GND2") (pintype "bidirectional"))
      (node (ref "J1") (pin "SHLD1") (pinfunction "SHLD_SHLD1") (pintype "bidirectional"))
      (node (ref "J1") (pin "SHLD2") (pinfunction "SHLD_SHLD2") (pintype "bidirectional"))
      (node (ref "J1") (pin "SHLD3") (pinfunction "SHLD_SHLD3") (pintype "bidirectional"))
      (node (ref "J1") (pin "SHLD4") (pinfunction "SHLD_SHLD4") (pintype "bidirectional"))
      (node (ref "J2") (pin "1") (pinfunction "1_1") (pintype "passive"))
      (node (ref "J3") (pin "1") (pinfunction "1_1") (pintype "passive"))
      (node (ref "LED1") (pin "C") (pinfunction "C_C") (pintype "passive"))
      (node (ref "LED11") (pin "A") (pinfunction "A_A") (pintype "passive"))
      (node (ref "LED12") (pin "A") (pinfunction "A_A") (pintype "passive"))
      (node (ref "LED13") (pin "A") (pinfunction "A_A") (pintype "passive"))
      (node (ref "LED14") (pin "A") (pinfunction "A_A") (pintype "passive"))
      (node (ref "LED15") (pin "A") (pinfunction "A_A") (pintype "passive"))
      (node (ref "LED16") (pin "A") (pinfunction "A_A") (pintype "passive"))
      (node (ref "LED17") (pin "A") (pinfunction "A_A") (pintype "passive"))
      (node (ref "LED18") (pin "A") (pinfunction "A_A") (pintype "passive"))
      (node (ref "LED2") (pin "C") (pinfunction "C_C") (pintype "passive"))
      (node (ref "Q1") (pin "2") (pinfunction "S_2") (pintype "bidirectional"))
      (node (ref "R17") (pin "1") (pinfunction "1_1") (pintype "passive"))
      (node (ref "R18") (pin "1") (pinfunction "1_1") (pintype "passive"))
      (node (ref "R35") (pin "1") (pinfunction "1_1") (pintype "passive"))
      (node (ref "R41") (pin "2") (pinfunction "2_2") (pintype "passive"))
      (node (ref "R9") (pin "1") (pinfunction "1_1") (pintype "passive"))
      (node (ref "RESET") (pin "A2") (pinfunction "1_A2") (pintype "passive"))
      (node (ref "T2") (pin "2") (pinfunction "E_2") (pintype "passive"))
      (node (ref "TP3") (pin "TP") (pinfunction "TP_TP") (pintype "input"))
      (node (ref "TP4") (pin "TP") (pinfunction "TP_TP") (pintype "input"))
      (node (ref "U$1") (pin "P$10") (pinfunction "LSS_P$10") (pintype "passive"))
      (node (ref "U$1") (pin "P$12") (pinfunction "LSS_2_P$12") (pintype "passive"))
      (node (ref "U$1") (pin "P$15") (pinfunction "SOA_P$15") (pintype "output"))
      (node (ref "U$1") (pin "P$16") (pinfunction "SOB_P$16") (pintype "output"))
      (node (ref "U$1") (pin "P$17") (pinfunction "SOC_P$17") (pintype "output"))
      (node (ref "U$1") (pin "P$18") (pinfunction "GND_P$18") (pintype "passive"))
      (node (ref "U$11") (pin "P$1") (pinfunction "P$1_P$1") (pintype "bidirectional"))
      (node (ref "U$14") (pin "P$1") (pinfunction "P$1_P$1") (pintype "bidirectional"))
      (node (ref "U$3") (pin "P$10") (pinfunction "LSS_P$10") (pintype "passive"))
      (node (ref "U$3") (pin "P$12") (pinfunction "LSS_2_P$12") (pintype "passive"))
      (node (ref "U$3") (pin "P$15") (pinfunction "SOA_P$15") (pintype "output"))
      (node (ref "U$3") (pin "P$16") (pinfunction "SOB_P$16") (pintype "output"))
      (node (ref "U$3") (pin "P$17") (pinfunction "SOC_P$17") (pintype "output"))
      (node (ref "U$3") (pin "P$18") (pinfunction "GND_P$18") (pintype "passive"))
      (node (ref "U$6") (pin "P$1") (pinfunction "SDO/SA0_P$1") (pintype "bidirectional"))
      (node (ref "U$6") (pin "P$2") (pinfunction "SDX_P$2") (pintype "bidirectional"))
      (node (ref "U$6") (pin "P$3") (pinfunction "SCX_P$3") (pintype "bidirectional"))
      (node (ref "U$6") (pin "P$6") (pinfunction "GND1_P$6") (pintype "bidirectional"))
      (node (ref "U$6") (pin "P$7") (pinfunction "GND2_P$7") (pintype "bidirectional"))
      (node (ref "U$7") (pin "P$1") (pinfunction "P$1_P$1") (pintype "bidirectional"))
      (node (ref "U$9") (pin "P$1") (pinfunction "P$1_P$1") (pintype "bidirectional"))
      (node (ref "U2") (pin "4") (pinfunction "GND_4") (pintype "bidirectional"))
      (node (ref "U3") (pin "12") (pinfunction "VSSA_12") (pintype "power_in"))
      (node (ref "U3") (pin "18") (pinfunction "VSS_2_18") (pintype "power_in"))
      (node (ref "U3") (pin "31") (pinfunction "VSS_3_31") (pintype "power_in"))
      (node (ref "U3") (pin "47") (pinfunction "VSS_4_47") (pintype "power_in"))
      (node (ref "U3") (pin "63") (pinfunction "VSS_63") (pintype "power_in"))
      (node (ref "U4") (pin "2") (pinfunction "GND_2") (pintype "bidirectional"))
      (node (ref "U4") (pin "PAD") (pinfunction "GND_PAD") (pintype "bidirectional"))
      (node (ref "USER") (pin "A2") (pinfunction "1_A2") (pintype "passive"))
    )
    (net (code "47") (name "Net-(J1-CC1)") (class "Default")
      (node (ref "J1") (pin "A5") (pinfunction "CC1_A5") (pintype "bidirectional"))
      (node (ref "R18") (pin "2") (pinfunction "2_2") (pintype "passive"))
    )
    (net (code "48") (name "Net-(J1-CC2)") (class "Default")
      (node (ref "J1") (pin "B5") (pinfunction "CC2_B5") (pintype "bidirectional"))
      (node (ref "R17") (pin "2") (pinfunction "2_2") (pintype "passive"))
    )
    (net (code "49") (name "Net-(L1-1)") (class "Default")
      (node (ref "C12") (pin "2") (pinfunction "2_2") (pintype "passive"))
      (node (ref "L1") (pin "P$1") (pinfunction "1_P$1") (pintype "passive"))
      (node (ref "U2") (pin "5") (pinfunction "SW_5") (pintype "bidirectional"))
    )
    (net (code "50") (name "Net-(LED1-PadA)") (class "Default")
      (node (ref "LED1") (pin "A") (pinfunction "A_A") (pintype "passive"))
      (node (ref "R12") (pin "1") (pinfunction "1_1") (pintype "passive"))
    )
    (net (code "51") (name "Net-(LED2-PadA)") (class "Default")
      (node (ref "LED2") (pin "A") (pinfunction "A_A") (pintype "passive"))
      (node (ref "R13") (pin "1") (pinfunction "1_1") (pintype "passive"))
    )
    (net (code "52") (name "Net-(LED3-PadA)") (class "Default")
      (node (ref "LED3") (pin "A") (pinfunction "A_A") (pintype "passive"))
      (node (ref "R19") (pin "1") (pinfunction "1_1") (pintype "passive"))
    )
    (net (code "53") (name "Net-(LED4-PadA)") (class "Default")
      (node (ref "LED4") (pin "A") (pinfunction "A_A") (pintype "passive"))
      (node (ref "R20") (pin "1") (pinfunction "1_1") (pintype "passive"))
    )
    (net (code "54") (name "Net-(LED5-PadA)") (class "Default")
      (node (ref "LED5") (pin "A") (pinfunction "A_A") (pintype "passive"))
      (node (ref "R21") (pin "1") (pinfunction "1_1") (pintype "passive"))
    )
    (net (code "55") (name "Net-(LED6-PadA)") (class "Default")
      (node (ref "LED6") (pin "A") (pinfunction "A_A") (pintype "passive"))
      (node (ref "R22") (pin "1") (pinfunction "1_1") (pintype "passive"))
    )
    (net (code "56") (name "Net-(LED7-PadA)") (class "Default")
      (node (ref "LED7") (pin "A") (pinfunction "A_A") (pintype "passive"))
      (node (ref "R23") (pin "1") (pinfunction "1_1") (pintype "passive"))
    )
    (net (code "57") (name "Net-(LED8-PadA)") (class "Default")
      (node (ref "LED8") (pin "A") (pinfunction "A_A") (pintype "passive"))
      (node (ref "R24") (pin "1") (pinfunction "1_1") (pintype "passive"))
    )
    (net (code "58") (name "Net-(LED9-PadA)") (class "Default")
      (node (ref "LED9") (pin "A") (pinfunction "A_A") (pintype "passive"))
      (node (ref "R25") (pin "1") (pinfunction "1_1") (pintype "passive"))
    )
    (net (code "59") (name "Net-(LED10-PadA)") (class "Default")
      (node (ref "LED10") (pin "A") (pinfunction "A_A") (pintype "passive"))
      (node (ref "R26") (pin "1") (pinfunction "1_1") (pintype "passive"))
    )
    (net (code "60") (name "Net-(Q1-D)") (class "Default")
      (node (ref "LED10") (pin "C") (pinfunction "C_C") (pintype "passive"))
      (node (ref "LED3") (pin "C") (pinfunction "C_C") (pintype "passive"))
      (node (ref "LED4") (pin "C") (pinfunction "C_C") (pintype "passive"))
      (node (ref "LED5") (pin "C") (pinfunction "C_C") (pintype "passive"))
      (node (ref "LED6") (pin "C") (pinfunction "C_C") (pintype "passive"))
      (node (ref "LED7") (pin "C") (pinfunction "C_C") (pintype "passive"))
      (node (ref "LED8") (pin "C") (pinfunction "C_C") (pintype "passive"))
      (node (ref "LED9") (pin "C") (pinfunction "C_C") (pintype "passive"))
      (node (ref "Q1") (pin "3") (pinfunction "D_3") (pintype "bidirectional"))
    )
    (net (code "61") (name "Net-(R5-Pad1)") (class "Default")
      (node (ref "R5") (pin "1") (pinfunction "1_1") (pintype "passive"))
      (node (ref "R6") (pin "1") (pinfunction "1_1") (pintype "passive"))
      (node (ref "R7") (pin "1") (pinfunction "1_1") (pintype "passive"))
      (node (ref "R8") (pin "1") (pinfunction "1_1") (pintype "passive"))
      (node (ref "T1") (pin "C") (pinfunction "C_C") (pintype "passive"))
    )
    (net (code "62") (name "Net-(R5-Pad2)") (class "Default")
      (node (ref "R5") (pin "2") (pinfunction "2_2") (pintype "passive"))
      (node (ref "U$10") (pin "P$2") (pinfunction "P$2_P$2") (pintype "bidirectional"))
    )
    (net (code "63") (name "Net-(R6-Pad2)") (class "Default")
      (node (ref "R6") (pin "2") (pinfunction "2_2") (pintype "passive"))
      (node (ref "U$13") (pin "P$2") (pinfunction "P$2_P$2") (pintype "bidirectional"))
    )
    (net (code "64") (name "Net-(R7-Pad2)") (class "Default")
      (node (ref "R7") (pin "2") (pinfunction "2_2") (pintype "passive"))
      (node (ref "U$12") (pin "P$2") (pinfunction "P$2_P$2") (pintype "bidirectional"))
    )
    (net (code "65") (name "Net-(R8-Pad2)") (class "Default")
      (node (ref "R8") (pin "2") (pinfunction "2_2") (pintype "passive"))
      (node (ref "U$8") (pin "P$2") (pinfunction "P$2_P$2") (pintype "bidirectional"))
    )
    (net (code "66") (name "Net-(T2-B)") (class "Default")
      (node (ref "R9") (pin "2") (pinfunction "2_2") (pintype "passive"))
      (node (ref "T1") (pin "E") (pinfunction "E_E") (pintype "passive"))
      (node (ref "T2") (pin "1") (pinfunction "B_1") (pintype "passive"))
      (node (ref "TP2") (pin "TP") (pinfunction "TP_TP") (pintype "input"))
    )
    (net (code "67") (name "Net-(T2-C)") (class "Default")
      (node (ref "R10") (pin "1") (pinfunction "1_1") (pintype "passive"))
      (node (ref "T1") (pin "B") (pinfunction "B_B") (pintype "passive"))
      (node (ref "T2") (pin "3") (pinfunction "C_3") (pintype "passive"))
    )
    (net (code "68") (name "Net-(U$1-CP1)") (class "Default")
      (node (ref "C23") (pin "2") (pinfunction "2_2") (pintype "passive"))
      (node (ref "U$1") (pin "P$20") (pinfunction "CP1_P$20") (pintype "passive"))
    )
    (net (code "69") (name "Net-(U$1-CP2)") (class "Default")
      (node (ref "C23") (pin "1") (pinfunction "1_1") (pintype "passive"))
      (node (ref "U$1") (pin "P$21") (pinfunction "CP2_P$21") (pintype "passive"))
    )
    (net (code "70") (name "Net-(U$1-VCP)") (class "Default")
      (node (ref "C24") (pin "2") (pinfunction "2_2") (pintype "passive"))
      (node (ref "U$1") (pin "P$19") (pinfunction "VCP_P$19") (pintype "output"))
    )
    (net (code "71") (name "Net-(U$1-VG)") (class "Default")
      (node (ref "C25") (pin "2") (pinfunction "2_2") (pintype "passive"))
      (node (ref "U$1") (pin "P$14") (pinfunction "VG_P$14") (pintype "power_in"))
    )
    (net (code "72") (name "Net-(U$3-CP1)") (class "Default")
      (node (ref "C26") (pin "2") (pinfunction "2_2") (pintype "passive"))
      (node (ref "U$3") (pin "P$20") (pinfunction "CP1_P$20") (pintype "passive"))
    )
    (net (code "73") (name "Net-(U$3-CP2)") (class "Default")
      (node (ref "C26") (pin "1") (pinfunction "1_1") (pintype "passive"))
      (node (ref "U$3") (pin "P$21") (pinfunction "CP2_P$21") (pintype "passive"))
    )
    (net (code "74") (name "Net-(U$3-VCP)") (class "Default")
      (node (ref "C27") (pin "2") (pinfunction "2_2") (pintype "passive"))
      (node (ref "U$3") (pin "P$19") (pinfunction "VCP_P$19") (pintype "output"))
    )
    (net (code "75") (name "Net-(U$3-VG)") (class "Default")
      (node (ref "C28") (pin "2") (pinfunction "2_2") (pintype "passive"))
      (node (ref "U$3") (pin "P$14") (pinfunction "VG_P$14") (pintype "power_in"))
    )
    (net (code "76") (name "Net-(U2-BST)") (class "Default")
      (node (ref "C12") (pin "1") (pinfunction "1_1") (pintype "passive"))
      (node (ref "U2") (pin "6") (pinfunction "BST_6") (pintype "bidirectional"))
    )
    (net (code "77") (name "Net-(U3A-PH0-OSC_IN)") (class "Default")
      (node (ref "C20") (pin "1") (pinfunction "1_1") (pintype "passive"))
      (node (ref "U3") (pin "5") (pinfunction "PH0-OSC_IN_5") (pintype "bidirectional"))
      (node (ref "Y1") (pin "3") (pinfunction "2_3") (pintype "passive"))
    )
    (net (code "78") (name "Net-(U3A-PH1-OSC_OUT)") (class "Default")
      (node (ref "C21") (pin "1") (pinfunction "1_1") (pintype "passive"))
      (node (ref "U3") (pin "6") (pinfunction "PH1-OSC_OUT_6") (pintype "bidirectional"))
      (node (ref "Y1") (pin "1") (pinfunction "1_1") (pintype "passive"))
    )
    (net (code "79") (name "Net-(U3B-VCAP_1)") (class "Default")
      (node (ref "C22") (pin "2") (pinfunction "2_2") (pintype "passive"))
      (node (ref "U3") (pin "30") (pinfunction "VCAP_1_30") (pintype "power_in"))
    )
    (net (code "80") (name "Net-(U4-DTR)") (class "Default")
      (node (ref "SJ1") (pin "1") (pinfunction "1_1") (pintype "passive"))
      (node (ref "U4") (pin "23") (pinfunction "DTR_23") (pintype "bidirectional"))
    )
    (net (code "81") (name "Net-(U4-RTS)") (class "Default")
      (node (ref "SJ2") (pin "1") (pinfunction "1_1") (pintype "passive"))
      (node (ref "U4") (pin "19") (pinfunction "RTS_19") (pintype "bidirectional"))
    )
    (net (code "82") (name "Net-(U4-VBUS)") (class "Default")
      (node (ref "R41") (pin "1") (pinfunction "1_1") (pintype "passive"))
      (node (ref "R42") (pin "2") (pinfunction "2_2") (pintype "passive"))
      (node (ref "U4") (pin "8") (pinfunction "VBUS_8") (pintype "bidirectional"))
    )
    (net (code "83") (name "Net-(U4-~{RSTB})") (class "Default")
      (node (ref "R40") (pin "2") (pinfunction "2_2") (pintype "passive"))
      (node (ref "U4") (pin "9") (pinfunction "~{RSTB}_9") (pintype "bidirectional"))
    )
    (net (code "84") (name "VCC") (class "Default")
      (node (ref "BATT") (pin "2") (pinfunction "2_2") (pintype "passive"))
      (node (ref "C10") (pin "+") (pinfunction "+_+") (pintype "passive"))
      (node (ref "C11") (pin "+") (pinfunction "+_+") (pintype "passive"))
      (node (ref "C13") (pin "2") (pinfunction "2_2") (pintype "passive"))
      (node (ref "C14") (pin "2") (pinfunction "2_2") (pintype "passive"))
      (node (ref "C24") (pin "1") (pinfunction "1_1") (pintype "passive"))
      (node (ref "C27") (pin "1") (pinfunction "1_1") (pintype "passive"))
      (node (ref "C4") (pin "1") (pinfunction "1_1") (pintype "passive"))
      (node (ref "C5") (pin "1") (pinfunction "1_1") (pintype "passive"))
      (node (ref "C6") (pin "1") (pinfunction "1_1") (pintype "passive"))
      (node (ref "C7") (pin "1") (pinfunction "1_1") (pintype "passive"))
      (node (ref "D1") (pin "C") (pinfunction "C_C") (pintype "passive"))
      (node (ref "U$1") (pin "P$23") (pinfunction "VIN_2_P$23") (pintype "power_in"))
      (node (ref "U$1") (pin "P$25") (pinfunction "VIN_P$25") (pintype "power_in"))
      (node (ref "U$10") (pin "P$1") (pinfunction "P$1_P$1") (pintype "bidirectional"))
      (node (ref "U$12") (pin "P$1") (pinfunction "P$1_P$1") (pintype "bidirectional"))
      (node (ref "U$13") (pin "P$1") (pinfunction "P$1_P$1") (pintype "bidirectional"))
      (node (ref "U$3") (pin "P$23") (pinfunction "VIN_2_P$23") (pintype "power_in"))
      (node (ref "U$3") (pin "P$25") (pinfunction "VIN_P$25") (pintype "power_in"))
      (node (ref "U$8") (pin "P$1") (pinfunction "P$1_P$1") (pintype "bidirectional"))
      (node (ref "U2") (pin "2") (pinfunction "EN_2") (pintype "bidirectional"))
      (node (ref "U2") (pin "3") (pinfunction "VIN_3") (pintype "bidirectional"))
    )
    (net (code "85") (name "unconnected-(U$1-NFAULT-PadP$1)") (class "Default")
      (node (ref "U$1") (pin "P$1") (pinfunction "NFAULT_P$1") (pintype "output"))
    )
    (net (code "86") (name "unconnected-(U$3-NFAULT-PadP$1)") (class "Default")
      (node (ref "U$3") (pin "P$1") (pinfunction "NFAULT_P$1") (pintype "output"))
    )
    (net (code "87") (name "unconnected-(U$6-INT1-PadP$4)") (class "Default")
      (node (ref "U$6") (pin "P$4") (pinfunction "INT1_P$4") (pintype "bidirectional"))
    )
    (net (code "88") (name "unconnected-(U$6-INT2-PadP$9)") (class "Default")
      (node (ref "U$6") (pin "P$9") (pinfunction "INT2_P$9") (pintype "bidirectional"))
    )
    (net (code "89") (name "unconnected-(U$6-NC1-PadP$10)") (class "Default")
      (node (ref "U$6") (pin "P$10") (pinfunction "NC1_P$10") (pintype "bidirectional"))
    )
    (net (code "90") (name "unconnected-(U$6-NC2-PadP$11)") (class "Default")
      (node (ref "U$6") (pin "P$11") (pinfunction "NC2_P$11") (pintype "bidirectional"))
    )
    (net (code "91") (name "unconnected-(U3A-PA8-Pad41)") (class "Default")
      (node (ref "U3") (pin "41") (pinfunction "PA8_41") (pintype "bidirectional"))
    )
    (net (code "92") (name "unconnected-(U3A-PA11-Pad44)") (class "Default")
      (node (ref "U3") (pin "44") (pinfunction "PA11_44") (pintype "bidirectional"))
    )
    (net (code "93") (name "unconnected-(U3A-PA12-Pad45)") (class "Default")
      (node (ref "U3") (pin "45") (pinfunction "PA12_45") (pintype "bidirectional"))
    )
    (net (code "94") (name "unconnected-(U3A-PA13-Pad46)") (class "Default")
      (node (ref "U3") (pin "46") (pinfunction "PA13_46") (pintype "bidirectional"))
    )
    (net (code "95") (name "unconnected-(U3A-PA14-Pad49)") (class "Default")
      (node (ref "U3") (pin "49") (pinfunction "PA14_49") (pintype "bidirectional"))
    )
    (net (code "96") (name "unconnected-(U3A-PA15-Pad50)") (class "Default")
      (node (ref "U3") (pin "50") (pinfunction "PA15_50") (pintype "bidirectional"))
    )
    (net (code "97") (name "unconnected-(U3A-PB3-Pad55)") (class "Default")
      (node (ref "U3") (pin "55") (pinfunction "PB3_55") (pintype "bidirectional"))
    )
    (net (code "98") (name "unconnected-(U3A-PB4-Pad56)") (class "Default")
      (node (ref "U3") (pin "56") (pinfunction "PB4_56") (pintype "bidirectional"))
    )
    (net (code "99") (name "unconnected-(U3A-PB12-Pad33)") (class "Default")
      (node (ref "U3") (pin "33") (pinfunction "PB12_33") (pintype "bidirectional"))
    )
    (net (code "100") (name "unconnected-(U3A-PB13-Pad34)") (class "Default")
      (node (ref "U3") (pin "34") (pinfunction "PB13_34") (pintype "bidirectional"))
    )
    (net (code "101") (name "unconnected-(U3A-PB14-Pad35)") (class "Default")
      (node (ref "U3") (pin "35") (pinfunction "PB14_35") (pintype "bidirectional"))
    )
    (net (code "102") (name "unconnected-(U3A-PB15-Pad36)") (class "Default")
      (node (ref "U3") (pin "36") (pinfunction "PB15_36") (pintype "bidirectional"))
    )
    (net (code "103") (name "unconnected-(U3A-PC13-Pad2)") (class "Default")
      (node (ref "U3") (pin "2") (pinfunction "PC13_2") (pintype "bidirectional"))
    )
    (net (code "104") (name "unconnected-(U3A-PC14-OSC32_IN-Pad3)") (class "Default")
      (node (ref "U3") (pin "3") (pinfunction "PC14-OSC32_IN_3") (pintype "bidirectional"))
    )
    (net (code "105") (name "unconnected-(U3A-PC15-OSC32_OUT-Pad4)") (class "Default")
      (node (ref "U3") (pin "4") (pinfunction "PC15-OSC32_OUT_4") (pintype "bidirectional"))
    )
    (net (code "106") (name "unconnected-(U3A-PD2-Pad54)") (class "Default")
      (node (ref "U3") (pin "54") (pinfunction "PD2_54") (pintype "bidirectional"))
    )
    (net (code "107") (name "unconnected-(U4-CTS-Pad18)") (class "Default")
      (node (ref "U4") (pin "18") (pinfunction "CTS_18") (pintype "bidirectional"))
    )
    (net (code "108") (name "unconnected-(U4-DCD-Pad24)") (class "Default")
      (node (ref "U4") (pin "24") (pinfunction "DCD_24") (pintype "bidirectional"))
    )
    (net (code "109") (name "unconnected-(U4-DSR-Pad22)") (class "Default")
      (node (ref "U4") (pin "22") (pinfunction "DSR_22") (pintype "bidirectional"))
    )
    (net (code "110") (name "unconnected-(U4-GPIO0{slash}TXT-Pad14)") (class "Default")
      (node (ref "U4") (pin "14") (pinfunction "GPIO0/TXT_14") (pintype "bidirectional"))
    )
    (net (code "111") (name "unconnected-(U4-GPIO1{slash}RXT-Pad13)") (class "Default")
      (node (ref "U4") (pin "13") (pinfunction "GPIO1/RXT_13") (pintype "bidirectional"))
    )
    (net (code "112") (name "unconnected-(U4-GPIO2{slash}RS485-Pad12)") (class "Default")
      (node (ref "U4") (pin "12") (pinfunction "GPIO2/RS485_12") (pintype "bidirectional"))
    )
    (net (code "113") (name "unconnected-(U4-GPIO3{slash}WAKEUP-Pad11)") (class "Default")
      (node (ref "U4") (pin "11") (pinfunction "GPIO3/WAKEUP_11") (pintype "bidirectional"))
    )
    (net (code "114") (name "unconnected-(U4-SUSPEND-Pad17)") (class "Default")
      (node (ref "U4") (pin "17") (pinfunction "SUSPEND_17") (pintype "bidirectional"))
    )
    (net (code "115") (name "unconnected-(U4-SUSPENDB-Pad15)") (class "Default")
      (node (ref "U4") (pin "15") (pinfunction "SUSPENDB_15") (pintype "bidirectional"))
    )
    (net (code "116") (name "unconnected-(U4-~{RI}{slash}CLK-Pad1)") (class "Default")
      (node (ref "U4") (pin "1") (pinfunction "~{RI}/CLK_1") (pintype "bidirectional"))
    )
  )
)
